# Crystal.net
KiCad netlist of a schematic drawn in Altium Designer
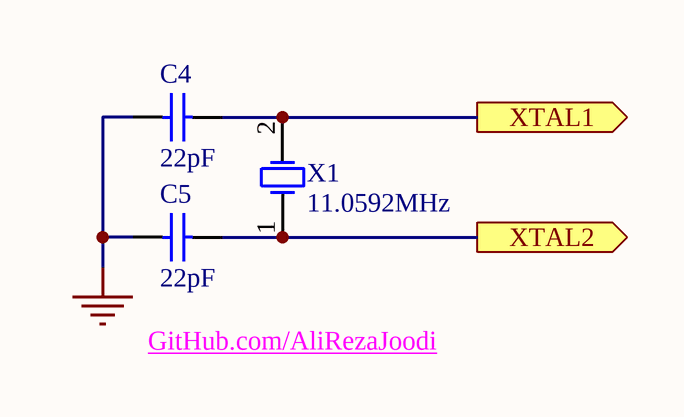
[diagram p0: Crystal.SchDoc]

(export (version "E")
  (design (tool "Eeschema 10.0.6"))
  (components
    (comp (ref "C4")
      (value "22pF")
      (footprint "CAPNTO2.54-3.05x1.78A")
      (description "Capacitor")
      (fields
        (field (name "MANUFACTURER") "Generic Components")
        (field (name "Comment") "Cap")
        (field (name "PUBLISHER") "Altium Limited")
      )
      (libsource (lib "Miscellaneous Devices") (part "Cap"))
    )
    (comp (ref "C5")
      (value "22pF")
      (footprint "CAPNTO2.54-3.05x1.78A")
      (description "Capacitor")
      (fields
        (field (name "MANUFACTURER") "Generic Components")
        (field (name "Comment") "Cap")
        (field (name "PUBLISHER") "Altium Limited")
      )
      (libsource (lib "Miscellaneous Devices") (part "Cap"))
    )
    (comp (ref "X1")
      (value "11.0592MHz")
      (footprint "XTAL_1")
      (description "Crystal Oscillator")
      (fields (field (name "MANUFACTURER") "Generic Components") (field (name "PUBLISHER") "Altium Limited"))
      (libsource (lib "Miscellaneous Devices") (part "XTAL"))
    )
  )
  (nets
    (net (code "1") (name "/XTAL1") (class "Default")
      (node (ref "C4") (pin "1") (pinfunction "1_1") (pintype "passive"))
      (node (ref "X1") (pin "2") (pinfunction "OSC2_2") (pintype "passive"))
    )
    (net (code "2") (name "/XTAL2") (class "Default")
      (node (ref "C5") (pin "1") (pinfunction "1_1") (pintype "passive"))
      (node (ref "X1") (pin "1") (pinfunction "OSC1_1") (pintype "passive"))
    )
    (net (code "3") (name "GND") (class "Default")
      (node (ref "C4") (pin "2") (pinfunction "2_2") (pintype "passive"))
      (node (ref "C5") (pin "2") (pinfunction "2_2") (pintype "passive"))
    )
  )
)
